# ATMEGA.net
KiCad netlist of a schematic drawn in Altium Designer
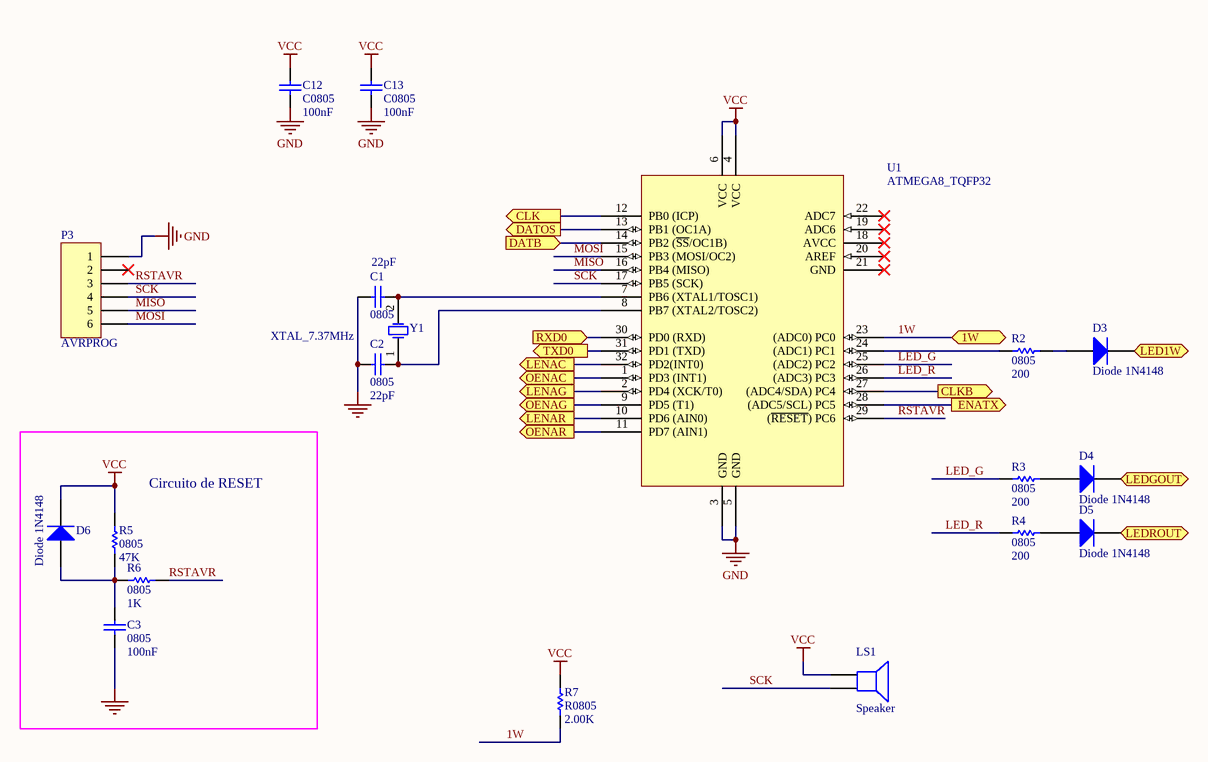
[diagram p0: ATMEGA.SchDoc]

(export (version "E")
  (design (tool "Eeschema 10.0.6"))
  (components
    (comp (ref "C1")
      (value "0805")
      (footprint "C0805C")
      (description "Cap 22pF")
      (fields
        (field (name "PART") "399-1113-1")
        (field (name "ALTIUM_VALUE") "22pF")
        (field (name "PUBLISHER") "Altium Limited")
      )
      (libsource (lib "PROPIASchlib") (part "Cap 0805 22pF"))
    )
    (comp (ref "C2")
      (value "0805")
      (footprint "C0805C")
      (description "Cap 22pF")
      (fields
        (field (name "PART") "399-1113-1")
        (field (name "ALTIUM_VALUE") "22pF")
        (field (name "PUBLISHER") "Altium Limited")
      )
      (libsource (lib "PROPIASchlib") (part "Cap 0805 22pF"))
    )
    (comp (ref "C3")
      (value "0805")
      (footprint "C0805C")
      (description "Cap 100nF 25V X7R")
      (fields
        (field (name "ALTIUM_VALUE") "100nF")
        (field (name "PART") "399-1170-1-ND")
        (field (name "PUBLISHER") "Altium Limited")
      )
      (libsource (lib "PROPIASchlib") (part "Cap 0805"))
    )
    (comp (ref "C12")
      (value "C0805")
      (footprint "C0805C")
      (description "Cap 100nF 25V X7R")
      (fields
        (field (name "PART") "399-1170-1-ND")
        (field (name "ALTIUM_VALUE") "100nF")
        (field (name "PUBLISHER") "Altium Limited")
      )
      (libsource (lib "PROPIASchlib") (part "Cap 0805 100nF"))
    )
    (comp (ref "C13")
      (value "C0805")
      (footprint "C0805C")
      (description "Cap 100nF 25V X7R")
      (fields
        (field (name "PART") "399-1170-1-ND")
        (field (name "ALTIUM_VALUE") "100nF")
        (field (name "PUBLISHER") "Altium Limited")
      )
      (libsource (lib "PROPIASchlib") (part "Cap 0805 100nF"))
    )
    (comp (ref "D3")
      (value "Diode 1N4148")
      (footprint "1N4148SMD")
      (description "1N4148")
      (fields (field (name "PART") "1N4148WTPMSCT") (field (name "PUBLISHER") "Altium Limited"))
      (libsource (lib "PROPIASchlib") (part "Diode 1N4148"))
    )
    (comp (ref "D4")
      (value "Diode 1N4148")
      (footprint "1N4148SMD")
      (description "1N4148")
      (fields (field (name "PART") "1N4148WTPMSCT") (field (name "PUBLISHER") "Altium Limited"))
      (libsource (lib "PROPIASchlib") (part "Diode 1N4148"))
    )
    (comp (ref "D5")
      (value "Diode 1N4148")
      (footprint "1N4148SMD")
      (description "1N4148")
      (fields (field (name "PART") "1N4148WTPMSCT") (field (name "PUBLISHER") "Altium Limited"))
      (libsource (lib "PROPIASchlib") (part "Diode 1N4148"))
    )
    (comp (ref "D6")
      (value "Diode 1N4148")
      (footprint "1N4148SMD")
      (description "1N4148")
      (fields (field (name "PART") "1N4148WTPMSCT") (field (name "PUBLISHER") "Altium Limited"))
      (libsource (lib "PROPIASchlib") (part "Diode 1N4148"))
    )
    (comp (ref "LS1")
      (value "Speaker")
      (footprint "PIN2")
      (description "Loudspeaker")
      (fields (field (name "PUBLISHER") "Altium Limited"))
      (libsource (lib "Miscellaneous Devices") (part "Speaker"))
    )
    (comp (ref "P3")
      (value "AVRPROG")
      (footprint "HDR1X6")
      (description "Header, 6-Pin")
      (fields (field (name "PUBLISHER") "Altium Limited"))
      (libsource (lib "Miscellaneous Connectors") (part "Header 6"))
    )
    (comp (ref "R2")
      (value "0805")
      (footprint "R0805")
      (description "Semiconductor Resistor")
      (fields
        (field (name "PART") "541-200ACT")
        (field (name "ALTIUM_VALUE") "200")
        (field (name "PUBLISHER") "Altium Limited")
      )
      (libsource (lib "PROPIASchlib") (part "Res 0805 200"))
    )
    (comp (ref "R3")
      (value "0805")
      (footprint "R0805")
      (description "Semiconductor Resistor")
      (fields
        (field (name "PART") "541-200ACT")
        (field (name "ALTIUM_VALUE") "200")
        (field (name "PUBLISHER") "Altium Limited")
      )
      (libsource (lib "PROPIASchlib") (part "Res 0805 200"))
    )
    (comp (ref "R4")
      (value "0805")
      (footprint "R0805")
      (description "Semiconductor Resistor")
      (fields
        (field (name "PART") "541-200ACT")
        (field (name "ALTIUM_VALUE") "200")
        (field (name "PUBLISHER") "Altium Limited")
      )
      (libsource (lib "PROPIASchlib") (part "Res 0805 200"))
    )
    (comp (ref "R5")
      (value "0805")
      (footprint "R0805")
      (description "Semiconductor Resistor")
      (fields
        (field (name "PART") "541-47KACT")
        (field (name "ALTIUM_VALUE") "47K")
        (field (name "PUBLISHER") "Altium Limited")
      )
      (libsource (lib "PROPIASchlib") (part "Res 0805 47K"))
    )
    (comp (ref "R6")
      (value "0805")
      (footprint "R0805")
      (description "Semiconductor Resistor")
      (fields
        (field (name "PART") "541-1.0KACT")
        (field (name "ALTIUM_VALUE") "1K")
        (field (name "PUBLISHER") "Altium Limited")
      )
      (libsource (lib "PROPIASchlib") (part "Res 0805 1K"))
    )
    (comp (ref "R7")
      (value "R0805")
      (footprint "R0805")
      (description "Semiconductor Resistor")
      (fields
        (field (name "PART") "311-2.0KARCT-ND")
        (field (name "ALTIUM_VALUE") "2.00K")
        (field (name "PUBLISHER") "Altium Limited")
      )
      (libsource (lib "PROPIASchlib") (part "Res 0805 2.00K"))
    )
    (comp (ref "U1")
      (value "ATMEGA8_TQFP32")
      (footprint "TQFP-32")
      (description "Atmel Microcontroller - Library created by carel..  <www.mpfreezone.com>")
      (libsource (lib "PROPIASchlib") (part "ATMEGA8_TQFP32"))
    )
    (comp (ref "Y1")
      (value "XTAL_7.37MHz")
      (footprint "CRYSTALSMD")
      (description "CRYSTAL 7.3728MHZ 18PF SMD")
      (fields (field (name "PART") "535-9088-1-ND") (field (name "PUBLISHER") "Altium Limited"))
      (libsource (lib "PROPIASchlib") (part "XTAL_7.37MHz"))
    )
  )
  (nets
    (net (code "1") (name "/1W") (class "Default")
      (node (ref "R7") (pin "1") (pinfunction "1_1") (pintype "passive"))
      (node (ref "U1") (pin "23") (pinfunction "(ADC0)_PC0_23") (pintype "bidirectional"))
    )
    (net (code "2") (name "/CLK") (class "Default")
      (node (ref "U1") (pin "12") (pinfunction "PB0_(ICP)_12") (pintype "passive"))
    )
    (net (code "3") (name "/CLKB") (class "Default")
      (node (ref "U1") (pin "27") (pinfunction "(ADC4/SDA)_PC4_27") (pintype "bidirectional"))
    )
    (net (code "4") (name "/DATB") (class "Default")
      (node (ref "U1") (pin "14") (pinfunction "PB2_(~{SS}/OC1B)_14") (pintype "bidirectional"))
    )
    (net (code "5") (name "/DATOS") (class "Default")
      (node (ref "U1") (pin "13") (pinfunction "PB1_(OC1A)_13") (pintype "bidirectional"))
    )
    (net (code "6") (name "/ENATX") (class "Default")
      (node (ref "U1") (pin "28") (pinfunction "(ADC5/SCL)_PC5_28") (pintype "bidirectional"))
    )
    (net (code "7") (name "/LED1W") (class "Default")
      (node (ref "D3") (pin "2") (pinfunction "K_2") (pintype "passive"))
    )
    (net (code "8") (name "/LEDGOUT") (class "Default")
      (node (ref "D4") (pin "2") (pinfunction "K_2") (pintype "passive"))
    )
    (net (code "9") (name "/LEDROUT") (class "Default")
      (node (ref "D5") (pin "2") (pinfunction "K_2") (pintype "passive"))
    )
    (net (code "10") (name "/LED_G") (class "Default")
      (node (ref "R3") (pin "1") (pinfunction "1_1") (pintype "passive"))
      (node (ref "U1") (pin "25") (pinfunction "(ADC2)_PC2_25") (pintype "bidirectional"))
    )
    (net (code "11") (name "/LED_R") (class "Default")
      (node (ref "R4") (pin "1") (pinfunction "1_1") (pintype "passive"))
      (node (ref "U1") (pin "26") (pinfunction "(ADC3)_PC3_26") (pintype "bidirectional"))
    )
    (net (code "12") (name "/LENAC") (class "Default")
      (node (ref "U1") (pin "32") (pinfunction "PD2(INT0)_32") (pintype "bidirectional"))
    )
    (net (code "13") (name "/LENAG") (class "Default")
      (node (ref "U1") (pin "2") (pinfunction "PD4_(XCK/T0)_2") (pintype "bidirectional"))
    )
    (net (code "14") (name "/LENAR") (class "Default")
      (node (ref "U1") (pin "10") (pinfunction "PD6_(AIN0)_10") (pintype "passive"))
    )
    (net (code "15") (name "/MISO") (class "Default")
      (node (ref "P3") (pin "5") (pinfunction "5_5") (pintype "passive"))
      (node (ref "U1") (pin "16") (pinfunction "PB4_(MISO)_16") (pintype "bidirectional"))
    )
    (net (code "16") (name "/MOSI") (class "Default")
      (node (ref "P3") (pin "6") (pinfunction "6_6") (pintype "passive"))
      (node (ref "U1") (pin "15") (pinfunction "PB3_(MOSI/OC2)_15") (pintype "bidirectional"))
    )
    (net (code "17") (name "/OENAC") (class "Default")
      (node (ref "U1") (pin "1") (pinfunction "PD3_(INT1)_1") (pintype "bidirectional"))
    )
    (net (code "18") (name "/OENAG") (class "Default")
      (node (ref "U1") (pin "9") (pinfunction "PD5_(T1)_9") (pintype "passive"))
    )
    (net (code "19") (name "/OENAR") (class "Default")
      (node (ref "U1") (pin "11") (pinfunction "PD7_(AIN1)_11") (pintype "passive"))
    )
    (net (code "20") (name "/RSTAVR") (class "Default")
      (node (ref "P3") (pin "3") (pinfunction "3_3") (pintype "passive"))
      (node (ref "R6") (pin "2") (pinfunction "2_2") (pintype "passive"))
      (node (ref "U1") (pin "29") (pinfunction "(~{RESET})_PC6_29") (pintype "bidirectional"))
    )
    (net (code "21") (name "/RXD0") (class "Default")
      (node (ref "U1") (pin "30") (pinfunction "PD0_(RXD)_30") (pintype "bidirectional"))
    )
    (net (code "22") (name "/SCK") (class "Default")
      (node (ref "LS1") (pin "2") (pinfunction "2_2") (pintype "passive"))
      (node (ref "P3") (pin "4") (pinfunction "4_4") (pintype "passive"))
      (node (ref "U1") (pin "17") (pinfunction "PB5_(SCK)_17") (pintype "bidirectional"))
    )
    (net (code "23") (name "/TXD0") (class "Default")
      (node (ref "U1") (pin "31") (pinfunction "PD1_(TXD)_31") (pintype "bidirectional"))
    )
    (net (code "24") (name "GND") (class "Default")
      (node (ref "C1") (pin "1") (pinfunction "1_1") (pintype "passive"))
      (node (ref "C12") (pin "1") (pinfunction "1_1") (pintype "passive"))
      (node (ref "C13") (pin "1") (pinfunction "1_1") (pintype "passive"))
      (node (ref "C2") (pin "1") (pinfunction "1_1") (pintype "passive"))
      (node (ref "C3") (pin "1") (pinfunction "1_1") (pintype "passive"))
      (node (ref "P3") (pin "1") (pinfunction "1_1") (pintype "passive"))
      (node (ref "U1") (pin "3") (pinfunction "GND_3") (pintype "passive"))
      (node (ref "U1") (pin "5") (pinfunction "GND_5") (pintype "power_in"))
    )
    (net (code "25") (name "Net-(D3-A)") (class "Default")
      (node (ref "D3") (pin "1") (pinfunction "A_1") (pintype "passive"))
      (node (ref "R2") (pin "2") (pinfunction "2_2") (pintype "passive"))
    )
    (net (code "26") (name "Net-(D4-A)") (class "Default")
      (node (ref "D4") (pin "1") (pinfunction "A_1") (pintype "passive"))
      (node (ref "R3") (pin "2") (pinfunction "2_2") (pintype "passive"))
    )
    (net (code "27") (name "Net-(D5-A)") (class "Default")
      (node (ref "D5") (pin "1") (pinfunction "A_1") (pintype "passive"))
      (node (ref "R4") (pin "2") (pinfunction "2_2") (pintype "passive"))
    )
    (net (code "28") (name "Net-(D6-A)") (class "Default")
      (node (ref "C3") (pin "2") (pinfunction "2_2") (pintype "passive"))
      (node (ref "D6") (pin "1") (pinfunction "A_1") (pintype "passive"))
      (node (ref "R5") (pin "1") (pinfunction "1_1") (pintype "passive"))
      (node (ref "R6") (pin "1") (pinfunction "1_1") (pintype "passive"))
    )
    (net (code "29") (name "Net-(U1-(ADC1)_PC1)") (class "Default")
      (node (ref "R2") (pin "1") (pinfunction "1_1") (pintype "passive"))
      (node (ref "U1") (pin "24") (pinfunction "(ADC1)_PC1_24") (pintype "bidirectional"))
    )
    (net (code "30") (name "Net-(U1-PB6_(XTAL1{slash}TOSC1))") (class "Default")
      (node (ref "C1") (pin "2") (pinfunction "2_2") (pintype "passive"))
      (node (ref "U1") (pin "7") (pinfunction "PB6_(XTAL1/TOSC1)_7") (pintype "passive"))
      (node (ref "Y1") (pin "2") (pinfunction "OSC2_2") (pintype "passive"))
    )
    (net (code "31") (name "Net-(U1-PB7_(XTAL2{slash}TOSC2))") (class "Default")
      (node (ref "C2") (pin "2") (pinfunction "2_2") (pintype "passive"))
      (node (ref "U1") (pin "8") (pinfunction "PB7_(XTAL2/TOSC2)_8") (pintype "passive"))
      (node (ref "Y1") (pin "1") (pinfunction "OSC1_1") (pintype "passive"))
    )
    (net (code "32") (name "VCC") (class "Default")
      (node (ref "C12") (pin "2") (pinfunction "2_2") (pintype "passive"))
      (node (ref "C13") (pin "2") (pinfunction "2_2") (pintype "passive"))
      (node (ref "D6") (pin "2") (pinfunction "K_2") (pintype "passive"))
      (node (ref "LS1") (pin "1") (pinfunction "1_1") (pintype "passive"))
      (node (ref "R5") (pin "2") (pinfunction "2_2") (pintype "passive"))
      (node (ref "R7") (pin "2") (pinfunction "2_2") (pintype "passive"))
      (node (ref "U1") (pin "4") (pinfunction "VCC_4") (pintype "power_in"))
      (node (ref "U1") (pin "6") (pinfunction "VCC_6") (pintype "passive"))
    )
    (net (code "33") (name "unconnected-(P3-Pad2)") (class "Default")
      (node (ref "P3") (pin "2") (pinfunction "2_2") (pintype "passive+no_connect"))
    )
    (net (code "34") (name "unconnected-(U1-ADC6-Pad19)") (class "Default")
      (node (ref "U1") (pin "19") (pinfunction "ADC6_19") (pintype "input+no_connect"))
    )
    (net (code "35") (name "unconnected-(U1-ADC7-Pad22)") (class "Default")
      (node (ref "U1") (pin "22") (pinfunction "ADC7_22") (pintype "input+no_connect"))
    )
    (net (code "36") (name "unconnected-(U1-AREF-Pad20)") (class "Default")
      (node (ref "U1") (pin "20") (pinfunction "AREF_20") (pintype "input+no_connect"))
    )
    (net (code "37") (name "unconnected-(U1-AVCC-Pad18)") (class "Default")
      (node (ref "U1") (pin "18") (pinfunction "AVCC_18") (pintype "passive+no_connect"))
    )
    (net (code "38") (name "unconnected-(U1-GND-Pad21)") (class "Default")
      (node (ref "U1") (pin "21") (pinfunction "GND_21") (pintype "passive+no_connect"))
    )
  )
)
